# Master.net
KiCad netlist of a schematic drawn in Altium Designer
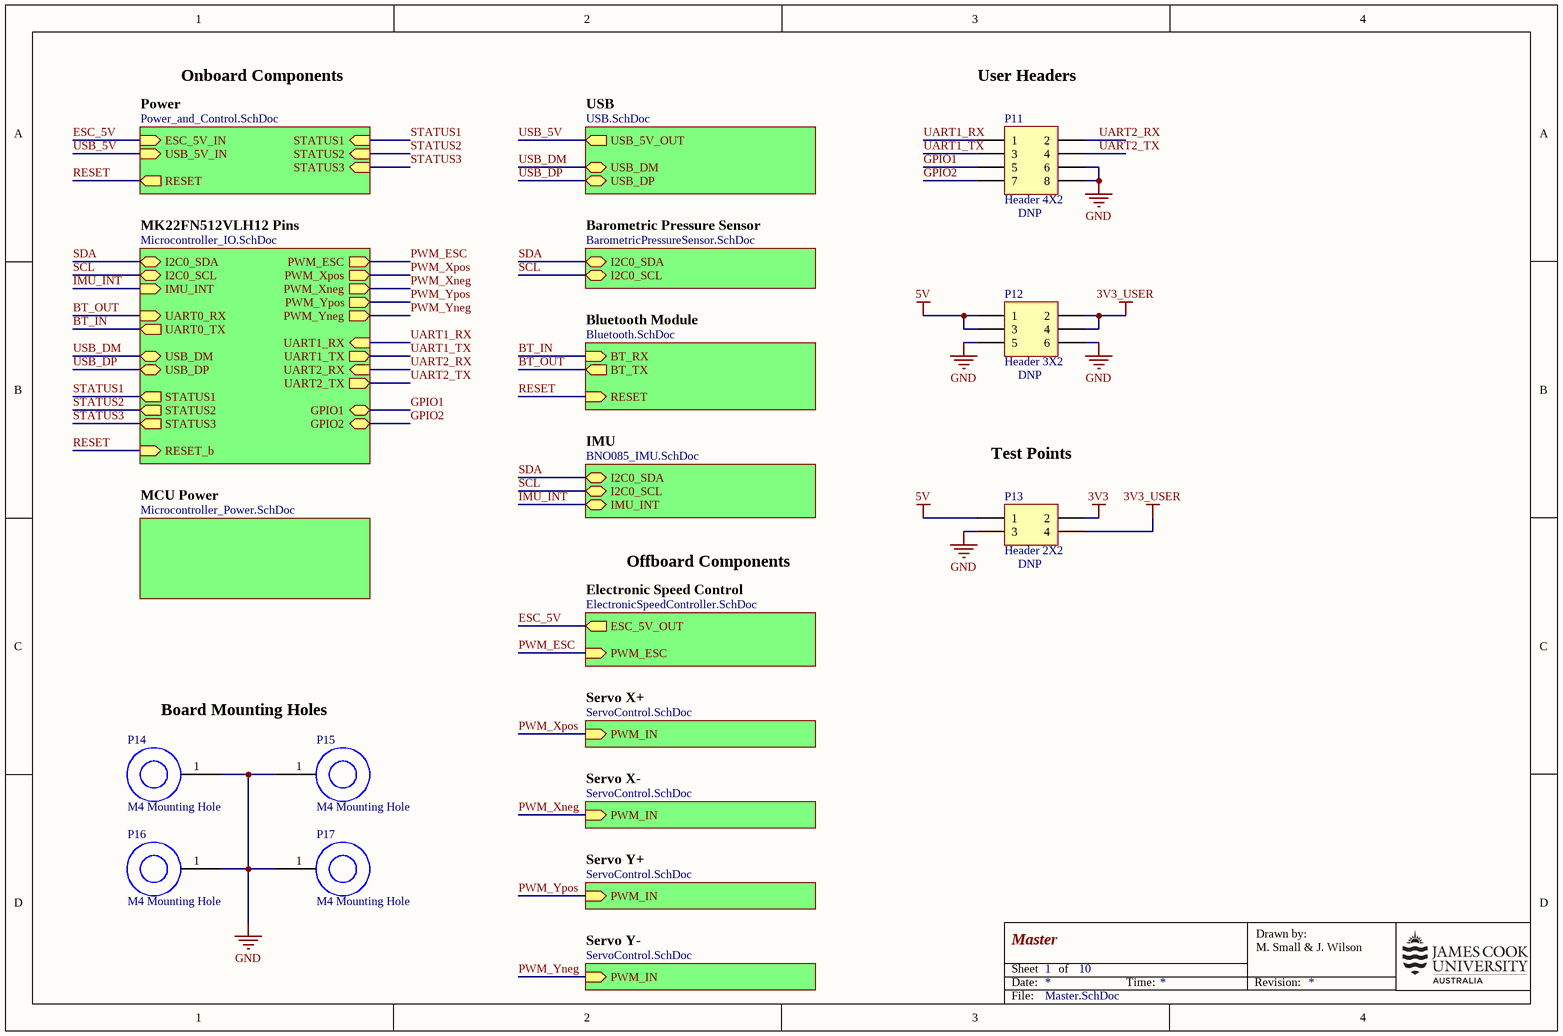
[diagram p0: Master.SchDoc]

(export (version "E")
  (design (tool "Eeschema 10.0.6"))
  (components
    (comp (ref "P11")
      (value "Header 4X2")
      (footprint "HDR2X4")
      (description "Header, 4-Pin, Dual row")
      (fields (field (name "PUBLISHER") "Altium Limited"))
      (libsource (lib "Miscellaneous Connectors") (part "Header 4X2"))
    )
    (comp (ref "P12")
      (value "Header 3X2")
      (footprint "HDR2X3")
      (description "Header, 3-Pin, Dual row")
      (fields (field (name "PUBLISHER") "Altium Limited"))
      (libsource (lib "Miscellaneous Connectors") (part "Header 3X2"))
    )
    (comp (ref "P13")
      (value "Header 2X2")
      (footprint "HDR2X2")
      (description "Header, 2-Pin, Dual row")
      (fields (field (name "PUBLISHER") "Altium Limited"))
      (libsource (lib "Miscellaneous Connectors") (part "Header 2X2"))
    )
    (comp (ref "P14")
      (value "M4 Mounting Hole")
      (footprint "M4 Mounting Hole")
      (description "M4 Mounting Hole, ID 3.62mm")
      (libsource (lib "CC3501_Misc_Symbols") (part "M4 Mounting Hole"))
    )
    (comp (ref "P15")
      (value "M4 Mounting Hole")
      (footprint "M4 Mounting Hole")
      (description "M4 Mounting Hole, ID 3.62mm")
      (libsource (lib "CC3501_Misc_Symbols") (part "M4 Mounting Hole"))
    )
    (comp (ref "P16")
      (value "M4 Mounting Hole")
      (footprint "M4 Mounting Hole")
      (description "M4 Mounting Hole, ID 3.62mm")
      (libsource (lib "CC3501_Misc_Symbols") (part "M4 Mounting Hole"))
    )
    (comp (ref "P17")
      (value "M4 Mounting Hole")
      (footprint "M4 Mounting Hole")
      (description "M4 Mounting Hole, ID 3.62mm")
      (libsource (lib "CC3501_Misc_Symbols") (part "M4 Mounting Hole"))
    )
  )
  (nets
    (net (code "5") (name "/GPIO1") (class "Default")
      (node (ref "P11") (pin "5") (pinfunction "5_5") (pintype "passive"))
    )
    (net (code "6") (name "/GPIO2") (class "Default")
      (node (ref "P11") (pin "7") (pinfunction "7_7") (pintype "passive"))
    )
    (net (code "19") (name "/UART1_RX") (class "Default")
      (node (ref "P11") (pin "1") (pinfunction "1_1") (pintype "passive"))
    )
    (net (code "20") (name "/UART1_TX") (class "Default")
      (node (ref "P11") (pin "3") (pinfunction "3_3") (pintype "passive"))
    )
    (net (code "21") (name "/UART2_RX") (class "Default")
      (node (ref "P11") (pin "2") (pinfunction "2_2") (pintype "passive"))
    )
    (net (code "22") (name "/UART2_TX") (class "Default")
      (node (ref "P11") (pin "4") (pinfunction "4_4") (pintype "passive"))
    )
    (net (code "26") (name "3V3") (class "Default")
      (node (ref "P13") (pin "2") (pinfunction "2_2") (pintype "passive"))
    )
    (net (code "27") (name "3V3_USER") (class "Default")
      (node (ref "P12") (pin "2") (pinfunction "2_2") (pintype "passive"))
      (node (ref "P12") (pin "4") (pinfunction "4_4") (pintype "passive"))
      (node (ref "P13") (pin "4") (pinfunction "4_4") (pintype "passive"))
    )
    (net (code "28") (name "5V") (class "Default")
      (node (ref "P12") (pin "1") (pinfunction "1_1") (pintype "passive"))
      (node (ref "P12") (pin "3") (pinfunction "3_3") (pintype "passive"))
      (node (ref "P13") (pin "1") (pinfunction "1_1") (pintype "passive"))
    )
    (net (code "29") (name "GND") (class "Default")
      (node (ref "P11") (pin "6") (pinfunction "6_6") (pintype "passive"))
      (node (ref "P11") (pin "8") (pinfunction "8_8") (pintype "passive"))
      (node (ref "P12") (pin "5") (pinfunction "5_5") (pintype "passive"))
      (node (ref "P12") (pin "6") (pinfunction "6_6") (pintype "passive"))
      (node (ref "P13") (pin "3") (pinfunction "3_3") (pintype "passive"))
      (node (ref "P14") (pin "1") (pintype "power_in"))
      (node (ref "P15") (pin "1") (pintype "power_in"))
      (node (ref "P16") (pin "1") (pintype "power_in"))
      (node (ref "P17") (pin "1") (pintype "power_in"))
    )
  )
)
